# Low_Current_Gate_Driver.net
KiCad netlist of a schematic drawn in Altium Designer
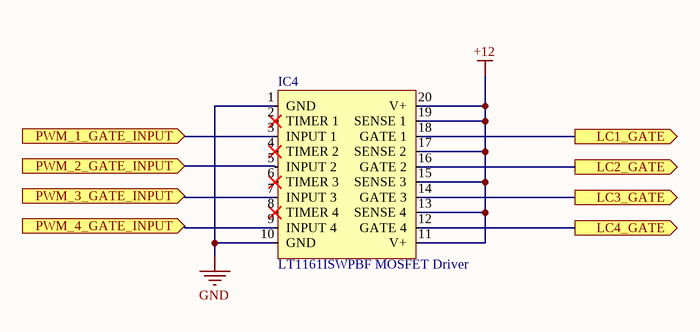
[diagram p0: Low_Current_Gate_Driver.SchDoc]

(export (version "E")
  (design (tool "Eeschema 10.0.6"))
  (components
    (comp (ref "IC4")
      (value "LT1161ISWPBF MOSFET Driver")
      (footprint "SO-20")
      (fields (field (name "CREATED_BY") "Eunice Bernardo"))
      (libsource (lib "Altium-Lib") (part "LT1161ISWPBF MOSFET Driver"))
    )
  )
  (nets
    (net (code "1") (name "+12") (class "Default")
      (node (ref "IC4") (pin "11") (pinfunction "V+_11") (pintype "input"))
      (node (ref "IC4") (pin "13") (pinfunction "SENSE_4_13") (pintype "input"))
      (node (ref "IC4") (pin "15") (pinfunction "SENSE_3_15") (pintype "input"))
      (node (ref "IC4") (pin "17") (pinfunction "SENSE_2_17") (pintype "input"))
      (node (ref "IC4") (pin "19") (pinfunction "SENSE_1_19") (pintype "input"))
      (node (ref "IC4") (pin "20") (pinfunction "V+_20") (pintype "input"))
    )
    (net (code "2") (name "/LC1_GATE") (class "Default")
      (node (ref "IC4") (pin "18") (pinfunction "GATE_1_18") (pintype "input"))
    )
    (net (code "3") (name "/LC2_GATE") (class "Default")
      (node (ref "IC4") (pin "16") (pinfunction "GATE_2_16") (pintype "input"))
    )
    (net (code "4") (name "/LC3_GATE") (class "Default")
      (node (ref "IC4") (pin "14") (pinfunction "GATE_3_14") (pintype "input"))
    )
    (net (code "5") (name "/LC4_GATE") (class "Default")
      (node (ref "IC4") (pin "12") (pinfunction "GATE_4_12") (pintype "input"))
    )
    (net (code "6") (name "/PWM_1_GATE_INPUT") (class "Default")
      (node (ref "IC4") (pin "3") (pinfunction "INPUT_1_3") (pintype "input"))
    )
    (net (code "7") (name "/PWM_2_GATE_INPUT") (class "Default")
      (node (ref "IC4") (pin "5") (pinfunction "INPUT_2_5") (pintype "input"))
    )
    (net (code "8") (name "/PWM_3_GATE_INPUT") (class "Default")
      (node (ref "IC4") (pin "7") (pinfunction "INPUT_3_7") (pintype "input"))
    )
    (net (code "9") (name "/PWM_4_GATE_INPUT") (class "Default")
      (node (ref "IC4") (pin "9") (pinfunction "INPUT_4_9") (pintype "input"))
    )
    (net (code "10") (name "GND") (class "Default")
      (node (ref "IC4") (pin "1") (pinfunction "GND_1") (pintype "input"))
      (node (ref "IC4") (pin "10") (pinfunction "GND_10") (pintype "input"))
    )
    (net (code "11") (name "unconnected-(IC4-TIMER_1-Pad2)") (class "Default")
      (node (ref "IC4") (pin "2") (pinfunction "TIMER_1_2") (pintype "input+no_connect"))
    )
    (net (code "12") (name "unconnected-(IC4-TIMER_2-Pad4)") (class "Default")
      (node (ref "IC4") (pin "4") (pinfunction "TIMER_2_4") (pintype "input+no_connect"))
    )
    (net (code "13") (name "unconnected-(IC4-TIMER_3-Pad6)") (class "Default")
      (node (ref "IC4") (pin "6") (pinfunction "TIMER_3_6") (pintype "input+no_connect"))
    )
    (net (code "14") (name "unconnected-(IC4-TIMER_4-Pad8)") (class "Default")
      (node (ref "IC4") (pin "8") (pinfunction "TIMER_4_8") (pintype "input+no_connect"))
    )
  )
)
